# usbmidilink.net
KiCad netlist of a schematic drawn in EAGLE
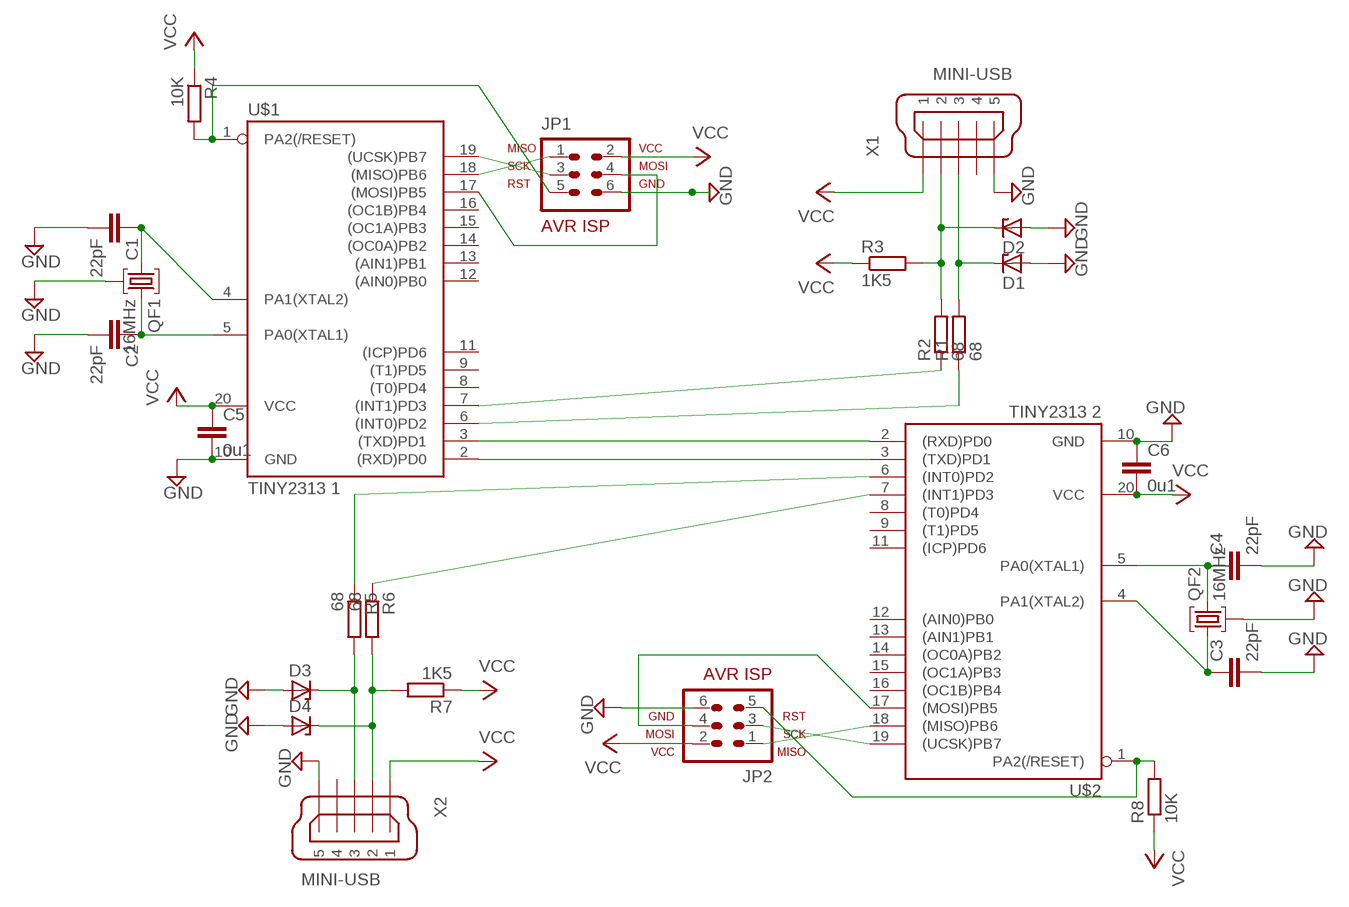
[diagram p0: schematic, sheet 1]

(export (version "E")
  (design (tool "Eeschema 10.0.6"))
  (components
    (comp (ref "C1")
      (value "22pF")
      (footprint "eagle-import:C2.5-4")
      (libsource (lib "eagle-import") (part "C2.5/4"))
    )
    (comp (ref "C2")
      (value "22pF")
      (footprint "eagle-import:C2.5-4")
      (libsource (lib "eagle-import") (part "C2.5/4"))
    )
    (comp (ref "C3")
      (value "22pF")
      (footprint "eagle-import:C2.5-4")
      (libsource (lib "eagle-import") (part "C2.5/4"))
    )
    (comp (ref "C4")
      (value "22pF")
      (footprint "eagle-import:C2.5-4")
      (libsource (lib "eagle-import") (part "C2.5/4"))
    )
    (comp (ref "C5")
      (value "0u1")
      (footprint "eagle-import:C2.5-4")
      (libsource (lib "eagle-import") (part "C2.5/4"))
    )
    (comp (ref "C6")
      (value "0u1")
      (footprint "eagle-import:C2.5-4")
      (libsource (lib "eagle-import") (part "C2.5/4"))
    )
    (comp (ref "D1")
      (value "ZENER-DIODEZD-5")
      (footprint "eagle-import:ZDIO-5")
      (libsource (lib "eagle-import") (part "ZENER-DIODEZD-5"))
    )
    (comp (ref "D2")
      (value "ZENER-DIODEZD-5")
      (footprint "eagle-import:ZDIO-5")
      (libsource (lib "eagle-import") (part "ZENER-DIODEZD-5"))
    )
    (comp (ref "D3")
      (value "ZENER-DIODEZD-5")
      (footprint "eagle-import:ZDIO-5")
      (libsource (lib "eagle-import") (part "ZENER-DIODEZD-5"))
    )
    (comp (ref "D4")
      (value "ZENER-DIODEZD-5")
      (footprint "eagle-import:ZDIO-5")
      (libsource (lib "eagle-import") (part "ZENER-DIODEZD-5"))
    )
    (comp (ref "JP1")
      (value "AVR-ISP-6VERT")
      (footprint "eagle-import:AVR-ISP-6")
      (libsource (lib "eagle-import") (part "AVR-ISP-6VERT"))
    )
    (comp (ref "JP2")
      (value "AVR-ISP-6VERT")
      (footprint "eagle-import:AVR-ISP-6")
      (libsource (lib "eagle-import") (part "AVR-ISP-6VERT"))
    )
    (comp (ref "QF1")
      (value "16MHz")
      (footprint "eagle-import:HC49U")
      (libsource (lib "eagle-import") (part "14M20BHC49T"))
    )
    (comp (ref "QF2")
      (value "16MHz")
      (footprint "eagle-import:HC49U")
      (libsource (lib "eagle-import") (part "14M20BHC49T"))
    )
    (comp (ref "R1")
      (value "68")
      (footprint "eagle-import:0204_5")
      (libsource (lib "eagle-import") (part "R-EU_0204/5"))
    )
    (comp (ref "R2")
      (value "68")
      (footprint "eagle-import:0204_5")
      (libsource (lib "eagle-import") (part "R-EU_0204/5"))
    )
    (comp (ref "R3")
      (value "1K5")
      (footprint "eagle-import:0204_5")
      (libsource (lib "eagle-import") (part "R-EU_0204/5"))
    )
    (comp (ref "R4")
      (value "10K")
      (footprint "eagle-import:0204_5")
      (libsource (lib "eagle-import") (part "R-EU_0204/5"))
    )
    (comp (ref "R5")
      (value "68")
      (footprint "eagle-import:0204_5")
      (libsource (lib "eagle-import") (part "R-EU_0204/5"))
    )
    (comp (ref "R6")
      (value "68")
      (footprint "eagle-import:0204_5")
      (libsource (lib "eagle-import") (part "R-EU_0204/5"))
    )
    (comp (ref "R7")
      (value "1K5")
      (footprint "eagle-import:0204_5")
      (libsource (lib "eagle-import") (part "R-EU_0204/5"))
    )
    (comp (ref "R8")
      (value "10K")
      (footprint "eagle-import:0204_5")
      (libsource (lib "eagle-import") (part "R-EU_0204/5"))
    )
    (comp (ref "U$1")
      (value "TINY2313 1")
      (footprint "eagle-import:DIL20")
      (libsource (lib "eagle-import") (part "TINY2313-P"))
    )
    (comp (ref "U$2")
      (value "TINY2313 2")
      (footprint "eagle-import:DIL20")
      (libsource (lib "eagle-import") (part "TINY2313-P"))
    )
    (comp (ref "X1")
      (value "MINI-USB")
      (footprint "eagle-import:32005-201")
      (libsource (lib "eagle-import") (part "MINI-USB-32005-201"))
    )
    (comp (ref "X2")
      (value "MINI-USB")
      (footprint "eagle-import:32005-201")
      (libsource (lib "eagle-import") (part "MINI-USB-32005-201"))
    )
  )
  (nets
    (net (code "1") (name "GND") (class "Default")
      (node (ref "C1") (pin "2") (pinfunction "2_2") (pintype "passive"))
      (node (ref "C2") (pin "2") (pinfunction "2_2") (pintype "passive"))
      (node (ref "C3") (pin "2") (pinfunction "2_2") (pintype "passive"))
      (node (ref "C4") (pin "2") (pinfunction "2_2") (pintype "passive"))
      (node (ref "C5") (pin "2") (pinfunction "2_2") (pintype "passive"))
      (node (ref "C6") (pin "1") (pinfunction "1_1") (pintype "passive"))
      (node (ref "D1") (pin "A") (pinfunction "A_A") (pintype "passive"))
      (node (ref "D2") (pin "A") (pinfunction "A_A") (pintype "passive"))
      (node (ref "D3") (pin "A") (pinfunction "A_A") (pintype "passive"))
      (node (ref "D4") (pin "A") (pinfunction "A_A") (pintype "passive"))
      (node (ref "JP1") (pin "6") (pinfunction "6_6") (pintype "passive"))
      (node (ref "JP2") (pin "6") (pinfunction "6_6") (pintype "passive"))
      (node (ref "QF1") (pin "2") (pinfunction "2_2") (pintype "passive"))
      (node (ref "QF2") (pin "2") (pinfunction "2_2") (pintype "passive"))
      (node (ref "U$1") (pin "10") (pinfunction "GND_10") (pintype "power_in"))
      (node (ref "U$2") (pin "10") (pinfunction "GND_10") (pintype "power_in"))
      (node (ref "X1") (pin "5") (pinfunction "5_5") (pintype "passive"))
      (node (ref "X2") (pin "5") (pinfunction "5_5") (pintype "passive"))
    )
    (net (code "2") (name "Net-(D1-PadC)") (class "Default")
      (node (ref "D1") (pin "C") (pinfunction "C_C") (pintype "passive"))
      (node (ref "R1") (pin "2") (pinfunction "2_2") (pintype "passive"))
      (node (ref "X1") (pin "3") (pinfunction "3_3") (pintype "passive"))
    )
    (net (code "3") (name "Net-(D2-PadC)") (class "Default")
      (node (ref "D2") (pin "C") (pinfunction "C_C") (pintype "passive"))
      (node (ref "R2") (pin "2") (pinfunction "2_2") (pintype "passive"))
      (node (ref "R3") (pin "2") (pinfunction "2_2") (pintype "passive"))
      (node (ref "X1") (pin "2") (pinfunction "2_2") (pintype "passive"))
    )
    (net (code "4") (name "Net-(D3-PadC)") (class "Default")
      (node (ref "D3") (pin "C") (pinfunction "C_C") (pintype "passive"))
      (node (ref "R5") (pin "2") (pinfunction "2_2") (pintype "passive"))
      (node (ref "X2") (pin "3") (pinfunction "3_3") (pintype "passive"))
    )
    (net (code "5") (name "Net-(D4-PadC)") (class "Default")
      (node (ref "D4") (pin "C") (pinfunction "C_C") (pintype "passive"))
      (node (ref "R6") (pin "2") (pinfunction "2_2") (pintype "passive"))
      (node (ref "R7") (pin "2") (pinfunction "2_2") (pintype "passive"))
      (node (ref "X2") (pin "2") (pinfunction "2_2") (pintype "passive"))
    )
    (net (code "6") (name "Net-(U$1-(INT0)PD2)") (class "Default")
      (node (ref "R1") (pin "1") (pinfunction "1_1") (pintype "passive"))
      (node (ref "U$1") (pin "6") (pinfunction "(INT0)PD2_6") (pintype "bidirectional"))
    )
    (net (code "7") (name "Net-(U$1-(INT1)PD3)") (class "Default")
      (node (ref "R2") (pin "1") (pinfunction "1_1") (pintype "passive"))
      (node (ref "U$1") (pin "7") (pinfunction "(INT1)PD3_7") (pintype "bidirectional"))
    )
    (net (code "8") (name "Net-(U$1-(MISO)PB6)") (class "Default")
      (node (ref "JP1") (pin "1") (pinfunction "1_1") (pintype "passive"))
      (node (ref "U$1") (pin "18") (pinfunction "(MISO)PB6_18") (pintype "bidirectional"))
    )
    (net (code "9") (name "Net-(U$1-(MOSI)PB5)") (class "Default")
      (node (ref "JP1") (pin "4") (pinfunction "4_4") (pintype "passive"))
      (node (ref "U$1") (pin "17") (pinfunction "(MOSI)PB5_17") (pintype "bidirectional"))
    )
    (net (code "10") (name "Net-(U$1-(RXD)PD0)") (class "Default")
      (node (ref "U$1") (pin "2") (pinfunction "(RXD)PD0_2") (pintype "bidirectional"))
      (node (ref "U$2") (pin "3") (pinfunction "(TXD)PD1_3") (pintype "bidirectional"))
    )
    (net (code "11") (name "Net-(U$1-(TXD)PD1)") (class "Default")
      (node (ref "U$1") (pin "3") (pinfunction "(TXD)PD1_3") (pintype "bidirectional"))
      (node (ref "U$2") (pin "2") (pinfunction "(RXD)PD0_2") (pintype "bidirectional"))
    )
    (net (code "12") (name "Net-(U$1-(UCSK)PB7)") (class "Default")
      (node (ref "JP1") (pin "3") (pinfunction "3_3") (pintype "passive"))
      (node (ref "U$1") (pin "19") (pinfunction "(UCSK)PB7_19") (pintype "bidirectional"))
    )
    (net (code "13") (name "Net-(U$1-PA0(XTAL1))") (class "Default")
      (node (ref "C2") (pin "1") (pinfunction "1_1") (pintype "passive"))
      (node (ref "QF1") (pin "3") (pinfunction "3_3") (pintype "passive"))
      (node (ref "U$1") (pin "5") (pinfunction "PA0(XTAL1)_5") (pintype "bidirectional"))
    )
    (net (code "14") (name "Net-(U$1-PA1(XTAL2))") (class "Default")
      (node (ref "C1") (pin "1") (pinfunction "1_1") (pintype "passive"))
      (node (ref "QF1") (pin "1") (pinfunction "1_1") (pintype "passive"))
      (node (ref "U$1") (pin "4") (pinfunction "PA1(XTAL2)_4") (pintype "bidirectional"))
    )
    (net (code "15") (name "Net-(U$1-PA2({slash}RESET))") (class "Default")
      (node (ref "JP1") (pin "5") (pinfunction "5_5") (pintype "passive"))
      (node (ref "R4") (pin "2") (pinfunction "2_2") (pintype "passive"))
      (node (ref "U$1") (pin "1") (pinfunction "PA2(/RESET)_1") (pintype "input"))
    )
    (net (code "16") (name "Net-(U$2-(INT0)PD2)") (class "Default")
      (node (ref "R5") (pin "1") (pinfunction "1_1") (pintype "passive"))
      (node (ref "U$2") (pin "6") (pinfunction "(INT0)PD2_6") (pintype "bidirectional"))
    )
    (net (code "17") (name "Net-(U$2-(INT1)PD3)") (class "Default")
      (node (ref "R6") (pin "1") (pinfunction "1_1") (pintype "passive"))
      (node (ref "U$2") (pin "7") (pinfunction "(INT1)PD3_7") (pintype "bidirectional"))
    )
    (net (code "18") (name "Net-(U$2-(MISO)PB6)") (class "Default")
      (node (ref "JP2") (pin "1") (pinfunction "1_1") (pintype "passive"))
      (node (ref "U$2") (pin "18") (pinfunction "(MISO)PB6_18") (pintype "bidirectional"))
    )
    (net (code "19") (name "Net-(U$2-(MOSI)PB5)") (class "Default")
      (node (ref "JP2") (pin "4") (pinfunction "4_4") (pintype "passive"))
      (node (ref "U$2") (pin "17") (pinfunction "(MOSI)PB5_17") (pintype "bidirectional"))
    )
    (net (code "20") (name "Net-(U$2-(UCSK)PB7)") (class "Default")
      (node (ref "JP2") (pin "3") (pinfunction "3_3") (pintype "passive"))
      (node (ref "U$2") (pin "19") (pinfunction "(UCSK)PB7_19") (pintype "bidirectional"))
    )
    (net (code "21") (name "Net-(U$2-PA0(XTAL1))") (class "Default")
      (node (ref "C4") (pin "1") (pinfunction "1_1") (pintype "passive"))
      (node (ref "QF2") (pin "3") (pinfunction "3_3") (pintype "passive"))
      (node (ref "U$2") (pin "5") (pinfunction "PA0(XTAL1)_5") (pintype "bidirectional"))
    )
    (net (code "22") (name "Net-(U$2-PA1(XTAL2))") (class "Default")
      (node (ref "C3") (pin "1") (pinfunction "1_1") (pintype "passive"))
      (node (ref "QF2") (pin "1") (pinfunction "1_1") (pintype "passive"))
      (node (ref "U$2") (pin "4") (pinfunction "PA1(XTAL2)_4") (pintype "bidirectional"))
    )
    (net (code "23") (name "Net-(U$2-PA2({slash}RESET))") (class "Default")
      (node (ref "JP2") (pin "5") (pinfunction "5_5") (pintype "passive"))
      (node (ref "R8") (pin "2") (pinfunction "2_2") (pintype "passive"))
      (node (ref "U$2") (pin "1") (pinfunction "PA2(/RESET)_1") (pintype "input"))
    )
    (net (code "24") (name "VCC") (class "Default")
      (node (ref "C5") (pin "1") (pinfunction "1_1") (pintype "passive"))
      (node (ref "C6") (pin "2") (pinfunction "2_2") (pintype "passive"))
      (node (ref "JP1") (pin "2") (pinfunction "2_2") (pintype "passive"))
      (node (ref "JP2") (pin "2") (pinfunction "2_2") (pintype "passive"))
      (node (ref "R3") (pin "1") (pinfunction "1_1") (pintype "passive"))
      (node (ref "R4") (pin "1") (pinfunction "1_1") (pintype "passive"))
      (node (ref "R7") (pin "1") (pinfunction "1_1") (pintype "passive"))
      (node (ref "R8") (pin "1") (pinfunction "1_1") (pintype "passive"))
      (node (ref "U$1") (pin "20") (pinfunction "VCC_20") (pintype "power_in"))
      (node (ref "U$2") (pin "20") (pinfunction "VCC_20") (pintype "power_in"))
      (node (ref "X1") (pin "1") (pinfunction "1_1") (pintype "passive"))
      (node (ref "X2") (pin "1") (pinfunction "1_1") (pintype "passive"))
    )
    (net (code "25") (name "unconnected-(U$1-(AIN0)PB0-Pad12)") (class "Default")
      (node (ref "U$1") (pin "12") (pinfunction "(AIN0)PB0_12") (pintype "bidirectional"))
    )
    (net (code "26") (name "unconnected-(U$1-(AIN1)PB1-Pad13)") (class "Default")
      (node (ref "U$1") (pin "13") (pinfunction "(AIN1)PB1_13") (pintype "bidirectional"))
    )
    (net (code "27") (name "unconnected-(U$1-(ICP)PD6-Pad11)") (class "Default")
      (node (ref "U$1") (pin "11") (pinfunction "(ICP)PD6_11") (pintype "bidirectional"))
    )
    (net (code "28") (name "unconnected-(U$1-(OC0A)PB2-Pad14)") (class "Default")
      (node (ref "U$1") (pin "14") (pinfunction "(OC0A)PB2_14") (pintype "bidirectional"))
    )
    (net (code "29") (name "unconnected-(U$1-(OC1A)PB3-Pad15)") (class "Default")
      (node (ref "U$1") (pin "15") (pinfunction "(OC1A)PB3_15") (pintype "bidirectional"))
    )
    (net (code "30") (name "unconnected-(U$1-(OC1B)PB4-Pad16)") (class "Default")
      (node (ref "U$1") (pin "16") (pinfunction "(OC1B)PB4_16") (pintype "bidirectional"))
    )
    (net (code "31") (name "unconnected-(U$1-(T0)PD4-Pad8)") (class "Default")
      (node (ref "U$1") (pin "8") (pinfunction "(T0)PD4_8") (pintype "bidirectional"))
    )
    (net (code "32") (name "unconnected-(U$1-(T1)PD5-Pad9)") (class "Default")
      (node (ref "U$1") (pin "9") (pinfunction "(T1)PD5_9") (pintype "bidirectional"))
    )
    (net (code "33") (name "unconnected-(U$2-(AIN0)PB0-Pad12)") (class "Default")
      (node (ref "U$2") (pin "12") (pinfunction "(AIN0)PB0_12") (pintype "bidirectional"))
    )
    (net (code "34") (name "unconnected-(U$2-(AIN1)PB1-Pad13)") (class "Default")
      (node (ref "U$2") (pin "13") (pinfunction "(AIN1)PB1_13") (pintype "bidirectional"))
    )
    (net (code "35") (name "unconnected-(U$2-(ICP)PD6-Pad11)") (class "Default")
      (node (ref "U$2") (pin "11") (pinfunction "(ICP)PD6_11") (pintype "bidirectional"))
    )
    (net (code "36") (name "unconnected-(U$2-(OC0A)PB2-Pad14)") (class "Default")
      (node (ref "U$2") (pin "14") (pinfunction "(OC0A)PB2_14") (pintype "bidirectional"))
    )
    (net (code "37") (name "unconnected-(U$2-(OC1A)PB3-Pad15)") (class "Default")
      (node (ref "U$2") (pin "15") (pinfunction "(OC1A)PB3_15") (pintype "bidirectional"))
    )
    (net (code "38") (name "unconnected-(U$2-(OC1B)PB4-Pad16)") (class "Default")
      (node (ref "U$2") (pin "16") (pinfunction "(OC1B)PB4_16") (pintype "bidirectional"))
    )
    (net (code "39") (name "unconnected-(U$2-(T0)PD4-Pad8)") (class "Default")
      (node (ref "U$2") (pin "8") (pinfunction "(T0)PD4_8") (pintype "bidirectional"))
    )
    (net (code "40") (name "unconnected-(U$2-(T1)PD5-Pad9)") (class "Default")
      (node (ref "U$2") (pin "9") (pinfunction "(T1)PD5_9") (pintype "bidirectional"))
    )
    (net (code "41") (name "unconnected-(X1-Pad4)") (class "Default")
      (node (ref "X1") (pin "4") (pinfunction "4_4") (pintype "passive"))
    )
    (net (code "42") (name "unconnected-(X2-Pad4)") (class "Default")
      (node (ref "X2") (pin "4") (pinfunction "4_4") (pintype "passive"))
    )
  )
)
